# Row.net
KiCad netlist of a schematic drawn in Altium Designer
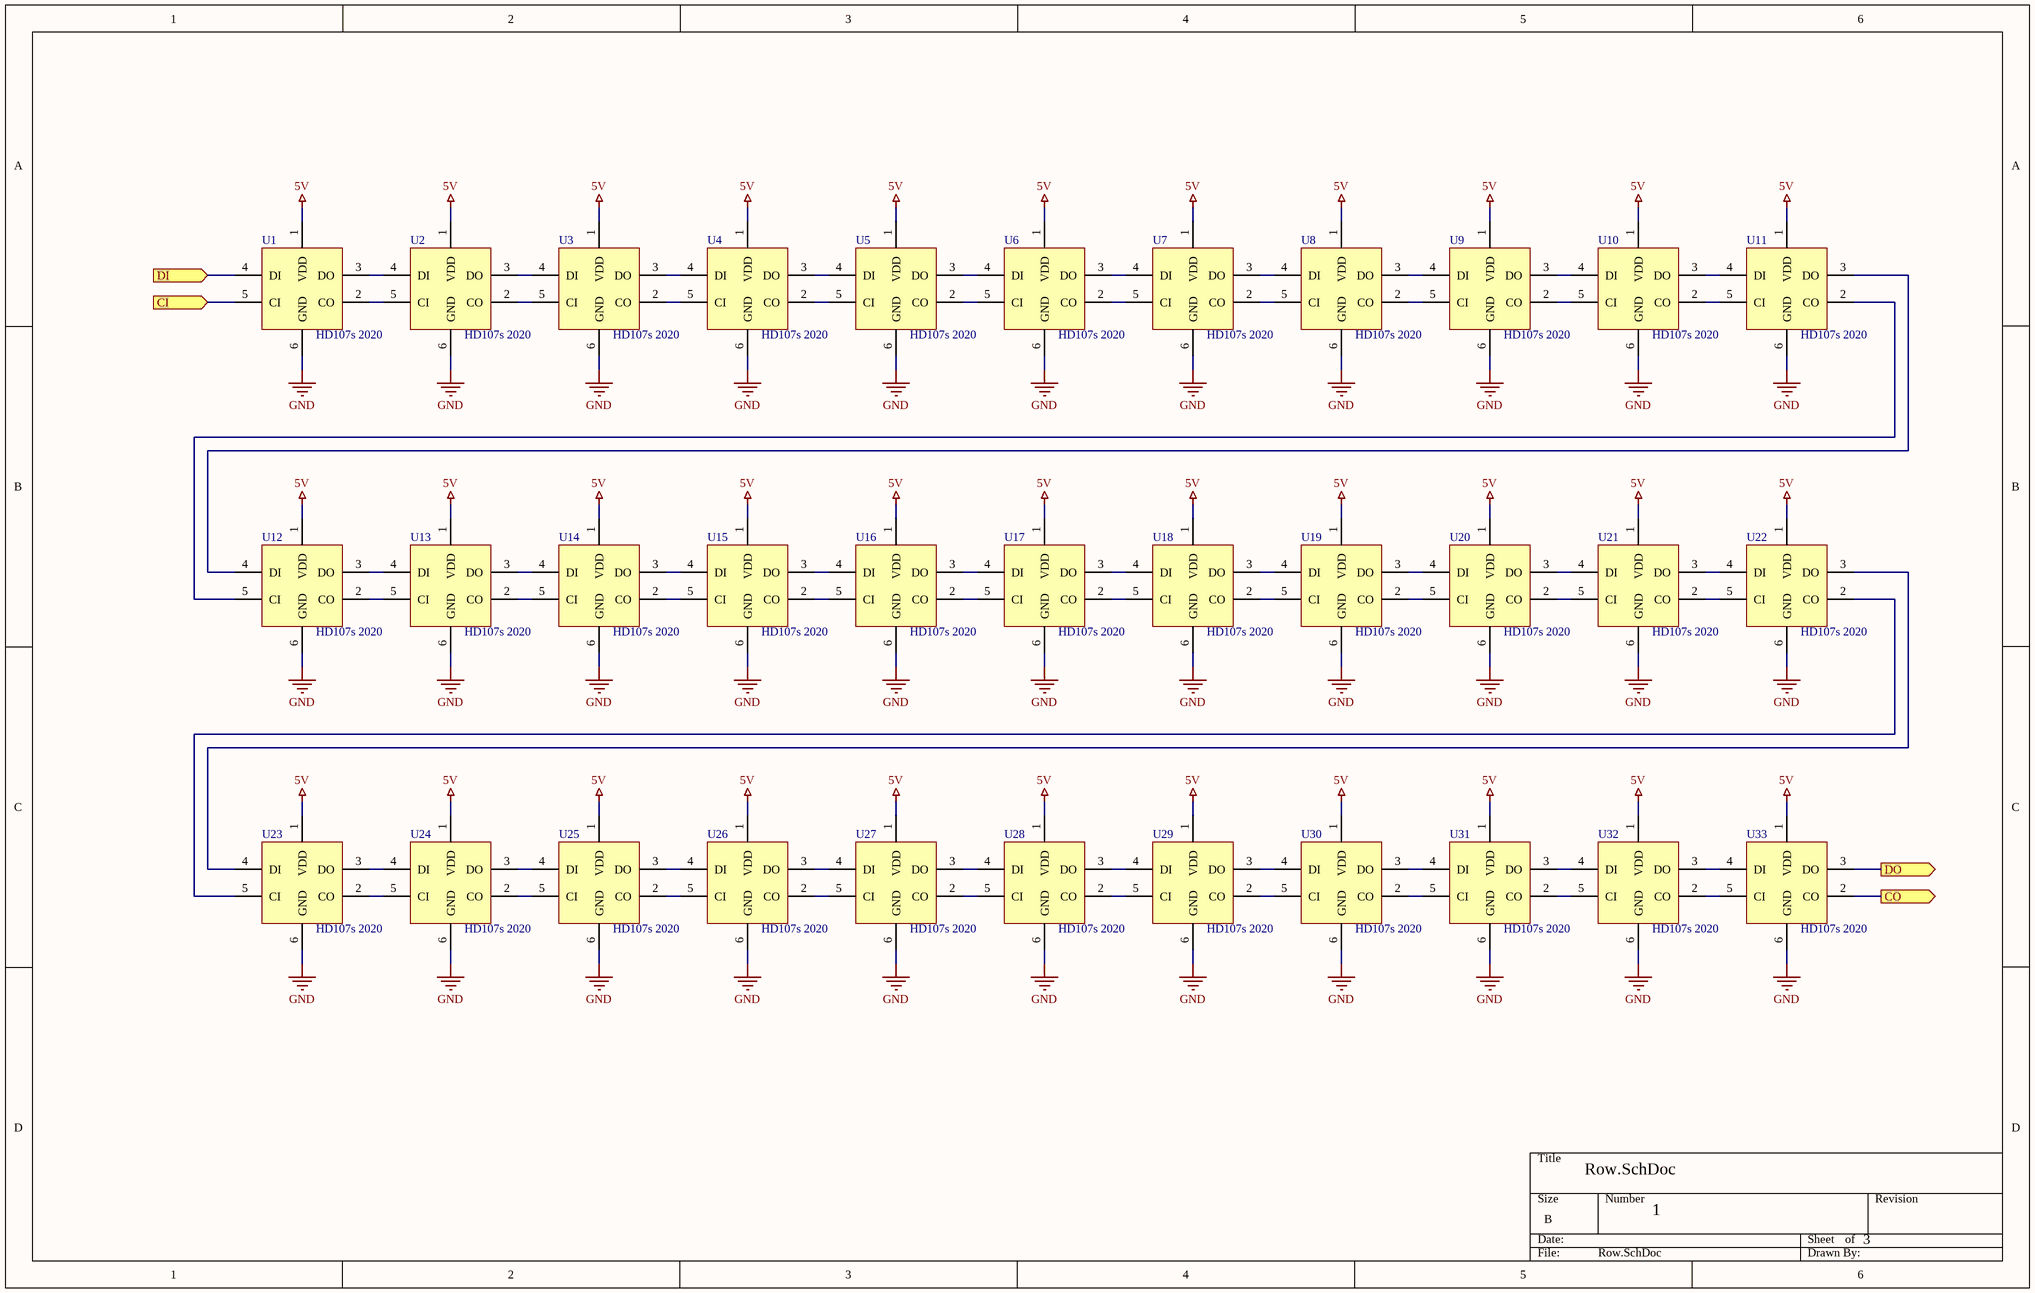
[diagram p0: Row.SchDoc]

(export (version "E")
  (design (tool "Eeschema 10.0.6"))
  (components
    (comp (ref "U1")
      (value "HD107s 2020")
      (footprint "LED_HD107s-2020")
      (description "8-pin type LED three-color RGB Dimming control")
      (fields (field (name "MP") "APA-102-2020-256-8") (field (name "MF") "iPixel LED Light Co."))
      (libsource (lib "IC") (part "HD107s-2020"))
    )
    (comp (ref "U2")
      (value "HD107s 2020")
      (footprint "LED_HD107s-2020")
      (description "8-pin type LED three-color RGB Dimming control")
      (fields (field (name "MP") "APA-102-2020-256-8") (field (name "MF") "iPixel LED Light Co."))
      (libsource (lib "IC") (part "HD107s-2020"))
    )
    (comp (ref "U3")
      (value "HD107s 2020")
      (footprint "LED_HD107s-2020")
      (description "8-pin type LED three-color RGB Dimming control")
      (fields (field (name "MP") "APA-102-2020-256-8") (field (name "MF") "iPixel LED Light Co."))
      (libsource (lib "IC") (part "HD107s-2020"))
    )
    (comp (ref "U4")
      (value "HD107s 2020")
      (footprint "LED_HD107s-2020")
      (description "8-pin type LED three-color RGB Dimming control")
      (fields (field (name "MP") "APA-102-2020-256-8") (field (name "MF") "iPixel LED Light Co."))
      (libsource (lib "IC") (part "HD107s-2020"))
    )
    (comp (ref "U5")
      (value "HD107s 2020")
      (footprint "LED_HD107s-2020")
      (description "8-pin type LED three-color RGB Dimming control")
      (fields (field (name "MP") "APA-102-2020-256-8") (field (name "MF") "iPixel LED Light Co."))
      (libsource (lib "IC") (part "HD107s-2020"))
    )
    (comp (ref "U6")
      (value "HD107s 2020")
      (footprint "LED_HD107s-2020")
      (description "8-pin type LED three-color RGB Dimming control")
      (fields (field (name "MP") "APA-102-2020-256-8") (field (name "MF") "iPixel LED Light Co."))
      (libsource (lib "IC") (part "HD107s-2020"))
    )
    (comp (ref "U7")
      (value "HD107s 2020")
      (footprint "LED_HD107s-2020")
      (description "8-pin type LED three-color RGB Dimming control")
      (fields (field (name "MP") "APA-102-2020-256-8") (field (name "MF") "iPixel LED Light Co."))
      (libsource (lib "IC") (part "HD107s-2020"))
    )
    (comp (ref "U8")
      (value "HD107s 2020")
      (footprint "LED_HD107s-2020")
      (description "8-pin type LED three-color RGB Dimming control")
      (fields (field (name "MP") "APA-102-2020-256-8") (field (name "MF") "iPixel LED Light Co."))
      (libsource (lib "IC") (part "HD107s-2020"))
    )
    (comp (ref "U9")
      (value "HD107s 2020")
      (footprint "LED_HD107s-2020")
      (description "8-pin type LED three-color RGB Dimming control")
      (fields (field (name "MP") "APA-102-2020-256-8") (field (name "MF") "iPixel LED Light Co."))
      (libsource (lib "IC") (part "HD107s-2020"))
    )
    (comp (ref "U10")
      (value "HD107s 2020")
      (footprint "LED_HD107s-2020")
      (description "8-pin type LED three-color RGB Dimming control")
      (fields (field (name "MP") "APA-102-2020-256-8") (field (name "MF") "iPixel LED Light Co."))
      (libsource (lib "IC") (part "HD107s-2020"))
    )
    (comp (ref "U11")
      (value "HD107s 2020")
      (footprint "LED_HD107s-2020")
      (description "8-pin type LED three-color RGB Dimming control")
      (fields (field (name "MP") "APA-102-2020-256-8") (field (name "MF") "iPixel LED Light Co."))
      (libsource (lib "IC") (part "HD107s-2020"))
    )
    (comp (ref "U12")
      (value "HD107s 2020")
      (footprint "LED_HD107s-2020")
      (description "8-pin type LED three-color RGB Dimming control")
      (fields (field (name "MP") "APA-102-2020-256-8") (field (name "MF") "iPixel LED Light Co."))
      (libsource (lib "IC") (part "HD107s-2020"))
    )
    (comp (ref "U13")
      (value "HD107s 2020")
      (footprint "LED_HD107s-2020")
      (description "8-pin type LED three-color RGB Dimming control")
      (fields (field (name "MP") "APA-102-2020-256-8") (field (name "MF") "iPixel LED Light Co."))
      (libsource (lib "IC") (part "HD107s-2020"))
    )
    (comp (ref "U14")
      (value "HD107s 2020")
      (footprint "LED_HD107s-2020")
      (description "8-pin type LED three-color RGB Dimming control")
      (fields (field (name "MP") "APA-102-2020-256-8") (field (name "MF") "iPixel LED Light Co."))
      (libsource (lib "IC") (part "HD107s-2020"))
    )
    (comp (ref "U15")
      (value "HD107s 2020")
      (footprint "LED_HD107s-2020")
      (description "8-pin type LED three-color RGB Dimming control")
      (fields (field (name "MP") "APA-102-2020-256-8") (field (name "MF") "iPixel LED Light Co."))
      (libsource (lib "IC") (part "HD107s-2020"))
    )
    (comp (ref "U16")
      (value "HD107s 2020")
      (footprint "LED_HD107s-2020")
      (description "8-pin type LED three-color RGB Dimming control")
      (fields (field (name "MP") "APA-102-2020-256-8") (field (name "MF") "iPixel LED Light Co."))
      (libsource (lib "IC") (part "HD107s-2020"))
    )
    (comp (ref "U17")
      (value "HD107s 2020")
      (footprint "LED_HD107s-2020")
      (description "8-pin type LED three-color RGB Dimming control")
      (fields (field (name "MP") "APA-102-2020-256-8") (field (name "MF") "iPixel LED Light Co."))
      (libsource (lib "IC") (part "HD107s-2020"))
    )
    (comp (ref "U18")
      (value "HD107s 2020")
      (footprint "LED_HD107s-2020")
      (description "8-pin type LED three-color RGB Dimming control")
      (fields (field (name "MP") "APA-102-2020-256-8") (field (name "MF") "iPixel LED Light Co."))
      (libsource (lib "IC") (part "HD107s-2020"))
    )
    (comp (ref "U19")
      (value "HD107s 2020")
      (footprint "LED_HD107s-2020")
      (description "8-pin type LED three-color RGB Dimming control")
      (fields (field (name "MP") "APA-102-2020-256-8") (field (name "MF") "iPixel LED Light Co."))
      (libsource (lib "IC") (part "HD107s-2020"))
    )
    (comp (ref "U20")
      (value "HD107s 2020")
      (footprint "LED_HD107s-2020")
      (description "8-pin type LED three-color RGB Dimming control")
      (fields (field (name "MP") "APA-102-2020-256-8") (field (name "MF") "iPixel LED Light Co."))
      (libsource (lib "IC") (part "HD107s-2020"))
    )
    (comp (ref "U21")
      (value "HD107s 2020")
      (footprint "LED_HD107s-2020")
      (description "8-pin type LED three-color RGB Dimming control")
      (fields (field (name "MP") "APA-102-2020-256-8") (field (name "MF") "iPixel LED Light Co."))
      (libsource (lib "IC") (part "HD107s-2020"))
    )
    (comp (ref "U22")
      (value "HD107s 2020")
      (footprint "LED_HD107s-2020")
      (description "8-pin type LED three-color RGB Dimming control")
      (fields (field (name "MP") "APA-102-2020-256-8") (field (name "MF") "iPixel LED Light Co."))
      (libsource (lib "IC") (part "HD107s-2020"))
    )
    (comp (ref "U23")
      (value "HD107s 2020")
      (footprint "LED_HD107s-2020")
      (description "8-pin type LED three-color RGB Dimming control")
      (fields (field (name "MP") "APA-102-2020-256-8") (field (name "MF") "iPixel LED Light Co."))
      (libsource (lib "IC") (part "HD107s-2020"))
    )
    (comp (ref "U24")
      (value "HD107s 2020")
      (footprint "LED_HD107s-2020")
      (description "8-pin type LED three-color RGB Dimming control")
      (fields (field (name "MP") "APA-102-2020-256-8") (field (name "MF") "iPixel LED Light Co."))
      (libsource (lib "IC") (part "HD107s-2020"))
    )
    (comp (ref "U25")
      (value "HD107s 2020")
      (footprint "LED_HD107s-2020")
      (description "8-pin type LED three-color RGB Dimming control")
      (fields (field (name "MP") "APA-102-2020-256-8") (field (name "MF") "iPixel LED Light Co."))
      (libsource (lib "IC") (part "HD107s-2020"))
    )
    (comp (ref "U26")
      (value "HD107s 2020")
      (footprint "LED_HD107s-2020")
      (description "8-pin type LED three-color RGB Dimming control")
      (fields (field (name "MP") "APA-102-2020-256-8") (field (name "MF") "iPixel LED Light Co."))
      (libsource (lib "IC") (part "HD107s-2020"))
    )
    (comp (ref "U27")
      (value "HD107s 2020")
      (footprint "LED_HD107s-2020")
      (description "8-pin type LED three-color RGB Dimming control")
      (fields (field (name "MP") "APA-102-2020-256-8") (field (name "MF") "iPixel LED Light Co."))
      (libsource (lib "IC") (part "HD107s-2020"))
    )
    (comp (ref "U28")
      (value "HD107s 2020")
      (footprint "LED_HD107s-2020")
      (description "8-pin type LED three-color RGB Dimming control")
      (fields (field (name "MP") "APA-102-2020-256-8") (field (name "MF") "iPixel LED Light Co."))
      (libsource (lib "IC") (part "HD107s-2020"))
    )
    (comp (ref "U29")
      (value "HD107s 2020")
      (footprint "LED_HD107s-2020")
      (description "8-pin type LED three-color RGB Dimming control")
      (fields (field (name "MP") "APA-102-2020-256-8") (field (name "MF") "iPixel LED Light Co."))
      (libsource (lib "IC") (part "HD107s-2020"))
    )
    (comp (ref "U30")
      (value "HD107s 2020")
      (footprint "LED_HD107s-2020")
      (description "8-pin type LED three-color RGB Dimming control")
      (fields (field (name "MP") "APA-102-2020-256-8") (field (name "MF") "iPixel LED Light Co."))
      (libsource (lib "IC") (part "HD107s-2020"))
    )
    (comp (ref "U31")
      (value "HD107s 2020")
      (footprint "LED_HD107s-2020")
      (description "8-pin type LED three-color RGB Dimming control")
      (fields (field (name "MP") "APA-102-2020-256-8") (field (name "MF") "iPixel LED Light Co."))
      (libsource (lib "IC") (part "HD107s-2020"))
    )
    (comp (ref "U32")
      (value "HD107s 2020")
      (footprint "LED_HD107s-2020")
      (description "8-pin type LED three-color RGB Dimming control")
      (fields (field (name "MP") "APA-102-2020-256-8") (field (name "MF") "iPixel LED Light Co."))
      (libsource (lib "IC") (part "HD107s-2020"))
    )
    (comp (ref "U33")
      (value "HD107s 2020")
      (footprint "LED_HD107s-2020")
      (description "8-pin type LED three-color RGB Dimming control")
      (fields (field (name "MP") "APA-102-2020-256-8") (field (name "MF") "iPixel LED Light Co."))
      (libsource (lib "IC") (part "HD107s-2020"))
    )
  )
  (nets
    (net (code "1") (name "/CI") (class "Default")
      (node (ref "U1") (pin "5") (pinfunction "CI_5") (pintype "passive"))
    )
    (net (code "2") (name "/CO") (class "Default")
      (node (ref "U33") (pin "2") (pinfunction "CO_2") (pintype "passive"))
    )
    (net (code "3") (name "/DI") (class "Default")
      (node (ref "U1") (pin "4") (pinfunction "DI_4") (pintype "passive"))
    )
    (net (code "4") (name "/DO") (class "Default")
      (node (ref "U33") (pin "3") (pinfunction "DO_3") (pintype "passive"))
    )
    (net (code "5") (name "5V") (class "Default")
      (node (ref "U1") (pin "1") (pinfunction "VDD_1") (pintype "power_in"))
      (node (ref "U10") (pin "1") (pinfunction "VDD_1") (pintype "power_in"))
      (node (ref "U11") (pin "1") (pinfunction "VDD_1") (pintype "power_in"))
      (node (ref "U12") (pin "1") (pinfunction "VDD_1") (pintype "power_in"))
      (node (ref "U13") (pin "1") (pinfunction "VDD_1") (pintype "power_in"))
      (node (ref "U14") (pin "1") (pinfunction "VDD_1") (pintype "power_in"))
      (node (ref "U15") (pin "1") (pinfunction "VDD_1") (pintype "power_in"))
      (node (ref "U16") (pin "1") (pinfunction "VDD_1") (pintype "power_in"))
      (node (ref "U17") (pin "1") (pinfunction "VDD_1") (pintype "power_in"))
      (node (ref "U18") (pin "1") (pinfunction "VDD_1") (pintype "power_in"))
      (node (ref "U19") (pin "1") (pinfunction "VDD_1") (pintype "power_in"))
      (node (ref "U2") (pin "1") (pinfunction "VDD_1") (pintype "power_in"))
      (node (ref "U20") (pin "1") (pinfunction "VDD_1") (pintype "power_in"))
      (node (ref "U21") (pin "1") (pinfunction "VDD_1") (pintype "power_in"))
      (node (ref "U22") (pin "1") (pinfunction "VDD_1") (pintype "power_in"))
      (node (ref "U23") (pin "1") (pinfunction "VDD_1") (pintype "power_in"))
      (node (ref "U24") (pin "1") (pinfunction "VDD_1") (pintype "power_in"))
      (node (ref "U25") (pin "1") (pinfunction "VDD_1") (pintype "power_in"))
      (node (ref "U26") (pin "1") (pinfunction "VDD_1") (pintype "power_in"))
      (node (ref "U27") (pin "1") (pinfunction "VDD_1") (pintype "power_in"))
      (node (ref "U28") (pin "1") (pinfunction "VDD_1") (pintype "power_in"))
      (node (ref "U29") (pin "1") (pinfunction "VDD_1") (pintype "power_in"))
      (node (ref "U3") (pin "1") (pinfunction "VDD_1") (pintype "power_in"))
      (node (ref "U30") (pin "1") (pinfunction "VDD_1") (pintype "power_in"))
      (node (ref "U31") (pin "1") (pinfunction "VDD_1") (pintype "power_in"))
      (node (ref "U32") (pin "1") (pinfunction "VDD_1") (pintype "power_in"))
      (node (ref "U33") (pin "1") (pinfunction "VDD_1") (pintype "power_in"))
      (node (ref "U4") (pin "1") (pinfunction "VDD_1") (pintype "power_in"))
      (node (ref "U5") (pin "1") (pinfunction "VDD_1") (pintype "power_in"))
      (node (ref "U6") (pin "1") (pinfunction "VDD_1") (pintype "power_in"))
      (node (ref "U7") (pin "1") (pinfunction "VDD_1") (pintype "power_in"))
      (node (ref "U8") (pin "1") (pinfunction "VDD_1") (pintype "power_in"))
      (node (ref "U9") (pin "1") (pinfunction "VDD_1") (pintype "power_in"))
    )
    (net (code "6") (name "GND") (class "Default")
      (node (ref "U1") (pin "6") (pinfunction "GND_6") (pintype "power_in"))
      (node (ref "U10") (pin "6") (pinfunction "GND_6") (pintype "power_in"))
      (node (ref "U11") (pin "6") (pinfunction "GND_6") (pintype "power_in"))
      (node (ref "U12") (pin "6") (pinfunction "GND_6") (pintype "power_in"))
      (node (ref "U13") (pin "6") (pinfunction "GND_6") (pintype "power_in"))
      (node (ref "U14") (pin "6") (pinfunction "GND_6") (pintype "power_in"))
      (node (ref "U15") (pin "6") (pinfunction "GND_6") (pintype "power_in"))
      (node (ref "U16") (pin "6") (pinfunction "GND_6") (pintype "power_in"))
      (node (ref "U17") (pin "6") (pinfunction "GND_6") (pintype "power_in"))
      (node (ref "U18") (pin "6") (pinfunction "GND_6") (pintype "power_in"))
      (node (ref "U19") (pin "6") (pinfunction "GND_6") (pintype "power_in"))
      (node (ref "U2") (pin "6") (pinfunction "GND_6") (pintype "power_in"))
      (node (ref "U20") (pin "6") (pinfunction "GND_6") (pintype "power_in"))
      (node (ref "U21") (pin "6") (pinfunction "GND_6") (pintype "power_in"))
      (node (ref "U22") (pin "6") (pinfunction "GND_6") (pintype "power_in"))
      (node (ref "U23") (pin "6") (pinfunction "GND_6") (pintype "power_in"))
      (node (ref "U24") (pin "6") (pinfunction "GND_6") (pintype "power_in"))
      (node (ref "U25") (pin "6") (pinfunction "GND_6") (pintype "power_in"))
      (node (ref "U26") (pin "6") (pinfunction "GND_6") (pintype "power_in"))
      (node (ref "U27") (pin "6") (pinfunction "GND_6") (pintype "power_in"))
      (node (ref "U28") (pin "6") (pinfunction "GND_6") (pintype "power_in"))
      (node (ref "U29") (pin "6") (pinfunction "GND_6") (pintype "power_in"))
      (node (ref "U3") (pin "6") (pinfunction "GND_6") (pintype "power_in"))
      (node (ref "U30") (pin "6") (pinfunction "GND_6") (pintype "power_in"))
      (node (ref "U31") (pin "6") (pinfunction "GND_6") (pintype "power_in"))
      (node (ref "U32") (pin "6") (pinfunction "GND_6") (pintype "power_in"))
      (node (ref "U33") (pin "6") (pinfunction "GND_6") (pintype "power_in"))
      (node (ref "U4") (pin "6") (pinfunction "GND_6") (pintype "power_in"))
      (node (ref "U5") (pin "6") (pinfunction "GND_6") (pintype "power_in"))
      (node (ref "U6") (pin "6") (pinfunction "GND_6") (pintype "power_in"))
      (node (ref "U7") (pin "6") (pinfunction "GND_6") (pintype "power_in"))
      (node (ref "U8") (pin "6") (pinfunction "GND_6") (pintype "power_in"))
      (node (ref "U9") (pin "6") (pinfunction "GND_6") (pintype "power_in"))
    )
    (net (code "7") (name "Net-(U1-CO)") (class "Default")
      (node (ref "U1") (pin "2") (pinfunction "CO_2") (pintype "passive"))
      (node (ref "U2") (pin "5") (pinfunction "CI_5") (pintype "passive"))
    )
    (net (code "8") (name "Net-(U1-DO)") (class "Default")
      (node (ref "U1") (pin "3") (pinfunction "DO_3") (pintype "passive"))
      (node (ref "U2") (pin "4") (pinfunction "DI_4") (pintype "passive"))
    )
    (net (code "9") (name "Net-(U2-CO)") (class "Default")
      (node (ref "U2") (pin "2") (pinfunction "CO_2") (pintype "passive"))
      (node (ref "U3") (pin "5") (pinfunction "CI_5") (pintype "passive"))
    )
    (net (code "10") (name "Net-(U2-DO)") (class "Default")
      (node (ref "U2") (pin "3") (pinfunction "DO_3") (pintype "passive"))
      (node (ref "U3") (pin "4") (pinfunction "DI_4") (pintype "passive"))
    )
    (net (code "11") (name "Net-(U3-CO)") (class "Default")
      (node (ref "U3") (pin "2") (pinfunction "CO_2") (pintype "passive"))
      (node (ref "U4") (pin "5") (pinfunction "CI_5") (pintype "passive"))
    )
    (net (code "12") (name "Net-(U3-DO)") (class "Default")
      (node (ref "U3") (pin "3") (pinfunction "DO_3") (pintype "passive"))
      (node (ref "U4") (pin "4") (pinfunction "DI_4") (pintype "passive"))
    )
    (net (code "13") (name "Net-(U4-CO)") (class "Default")
      (node (ref "U4") (pin "2") (pinfunction "CO_2") (pintype "passive"))
      (node (ref "U5") (pin "5") (pinfunction "CI_5") (pintype "passive"))
    )
    (net (code "14") (name "Net-(U4-DO)") (class "Default")
      (node (ref "U4") (pin "3") (pinfunction "DO_3") (pintype "passive"))
      (node (ref "U5") (pin "4") (pinfunction "DI_4") (pintype "passive"))
    )
    (net (code "15") (name "Net-(U5-CO)") (class "Default")
      (node (ref "U5") (pin "2") (pinfunction "CO_2") (pintype "passive"))
      (node (ref "U6") (pin "5") (pinfunction "CI_5") (pintype "passive"))
    )
    (net (code "16") (name "Net-(U5-DO)") (class "Default")
      (node (ref "U5") (pin "3") (pinfunction "DO_3") (pintype "passive"))
      (node (ref "U6") (pin "4") (pinfunction "DI_4") (pintype "passive"))
    )
    (net (code "17") (name "Net-(U6-CO)") (class "Default")
      (node (ref "U6") (pin "2") (pinfunction "CO_2") (pintype "passive"))
      (node (ref "U7") (pin "5") (pinfunction "CI_5") (pintype "passive"))
    )
    (net (code "18") (name "Net-(U6-DO)") (class "Default")
      (node (ref "U6") (pin "3") (pinfunction "DO_3") (pintype "passive"))
      (node (ref "U7") (pin "4") (pinfunction "DI_4") (pintype "passive"))
    )
    (net (code "19") (name "Net-(U7-CO)") (class "Default")
      (node (ref "U7") (pin "2") (pinfunction "CO_2") (pintype "passive"))
      (node (ref "U8") (pin "5") (pinfunction "CI_5") (pintype "passive"))
    )
    (net (code "20") (name "Net-(U7-DO)") (class "Default")
      (node (ref "U7") (pin "3") (pinfunction "DO_3") (pintype "passive"))
      (node (ref "U8") (pin "4") (pinfunction "DI_4") (pintype "passive"))
    )
    (net (code "21") (name "Net-(U8-CO)") (class "Default")
      (node (ref "U8") (pin "2") (pinfunction "CO_2") (pintype "passive"))
      (node (ref "U9") (pin "5") (pinfunction "CI_5") (pintype "passive"))
    )
    (net (code "22") (name "Net-(U8-DO)") (class "Default")
      (node (ref "U8") (pin "3") (pinfunction "DO_3") (pintype "passive"))
      (node (ref "U9") (pin "4") (pinfunction "DI_4") (pintype "passive"))
    )
    (net (code "23") (name "Net-(U10-CI)") (class "Default")
      (node (ref "U10") (pin "5") (pinfunction "CI_5") (pintype "passive"))
      (node (ref "U9") (pin "2") (pinfunction "CO_2") (pintype "passive"))
    )
    (net (code "24") (name "Net-(U10-CO)") (class "Default")
      (node (ref "U10") (pin "2") (pinfunction "CO_2") (pintype "passive"))
      (node (ref "U11") (pin "5") (pinfunction "CI_5") (pintype "passive"))
    )
    (net (code "25") (name "Net-(U10-DI)") (class "Default")
      (node (ref "U10") (pin "4") (pinfunction "DI_4") (pintype "passive"))
      (node (ref "U9") (pin "3") (pinfunction "DO_3") (pintype "passive"))
    )
    (net (code "26") (name "Net-(U10-DO)") (class "Default")
      (node (ref "U10") (pin "3") (pinfunction "DO_3") (pintype "passive"))
      (node (ref "U11") (pin "4") (pinfunction "DI_4") (pintype "passive"))
    )
    (net (code "27") (name "Net-(U11-CO)") (class "Default")
      (node (ref "U11") (pin "2") (pinfunction "CO_2") (pintype "passive"))
      (node (ref "U12") (pin "5") (pinfunction "CI_5") (pintype "passive"))
    )
    (net (code "28") (name "Net-(U11-DO)") (class "Default")
      (node (ref "U11") (pin "3") (pinfunction "DO_3") (pintype "passive"))
      (node (ref "U12") (pin "4") (pinfunction "DI_4") (pintype "passive"))
    )
    (net (code "29") (name "Net-(U12-CO)") (class "Default")
      (node (ref "U12") (pin "2") (pinfunction "CO_2") (pintype "passive"))
      (node (ref "U13") (pin "5") (pinfunction "CI_5") (pintype "passive"))
    )
    (net (code "30") (name "Net-(U12-DO)") (class "Default")
      (node (ref "U12") (pin "3") (pinfunction "DO_3") (pintype "passive"))
      (node (ref "U13") (pin "4") (pinfunction "DI_4") (pintype "passive"))
    )
    (net (code "31") (name "Net-(U13-CO)") (class "Default")
      (node (ref "U13") (pin "2") (pinfunction "CO_2") (pintype "passive"))
      (node (ref "U14") (pin "5") (pinfunction "CI_5") (pintype "passive"))
    )
    (net (code "32") (name "Net-(U13-DO)") (class "Default")
      (node (ref "U13") (pin "3") (pinfunction "DO_3") (pintype "passive"))
      (node (ref "U14") (pin "4") (pinfunction "DI_4") (pintype "passive"))
    )
    (net (code "33") (name "Net-(U14-CO)") (class "Default")
      (node (ref "U14") (pin "2") (pinfunction "CO_2") (pintype "passive"))
      (node (ref "U15") (pin "5") (pinfunction "CI_5") (pintype "passive"))
    )
    (net (code "34") (name "Net-(U14-DO)") (class "Default")
      (node (ref "U14") (pin "3") (pinfunction "DO_3") (pintype "passive"))
      (node (ref "U15") (pin "4") (pinfunction "DI_4") (pintype "passive"))
    )
    (net (code "35") (name "Net-(U15-CO)") (class "Default")
      (node (ref "U15") (pin "2") (pinfunction "CO_2") (pintype "passive"))
      (node (ref "U16") (pin "5") (pinfunction "CI_5") (pintype "passive"))
    )
    (net (code "36") (name "Net-(U15-DO)") (class "Default")
      (node (ref "U15") (pin "3") (pinfunction "DO_3") (pintype "passive"))
      (node (ref "U16") (pin "4") (pinfunction "DI_4") (pintype "passive"))
    )
    (net (code "37") (name "Net-(U16-CO)") (class "Default")
      (node (ref "U16") (pin "2") (pinfunction "CO_2") (pintype "passive"))
      (node (ref "U17") (pin "5") (pinfunction "CI_5") (pintype "passive"))
    )
    (net (code "38") (name "Net-(U16-DO)") (class "Default")
      (node (ref "U16") (pin "3") (pinfunction "DO_3") (pintype "passive"))
      (node (ref "U17") (pin "4") (pinfunction "DI_4") (pintype "passive"))
    )
    (net (code "39") (name "Net-(U17-CO)") (class "Default")
      (node (ref "U17") (pin "2") (pinfunction "CO_2") (pintype "passive"))
      (node (ref "U18") (pin "5") (pinfunction "CI_5") (pintype "passive"))
    )
    (net (code "40") (name "Net-(U17-DO)") (class "Default")
      (node (ref "U17") (pin "3") (pinfunction "DO_3") (pintype "passive"))
      (node (ref "U18") (pin "4") (pinfunction "DI_4") (pintype "passive"))
    )
    (net (code "41") (name "Net-(U18-CO)") (class "Default")
      (node (ref "U18") (pin "2") (pinfunction "CO_2") (pintype "passive"))
      (node (ref "U19") (pin "5") (pinfunction "CI_5") (pintype "passive"))
    )
    (net (code "42") (name "Net-(U18-DO)") (class "Default")
      (node (ref "U18") (pin "3") (pinfunction "DO_3") (pintype "passive"))
      (node (ref "U19") (pin "4") (pinfunction "DI_4") (pintype "passive"))
    )
    (net (code "43") (name "Net-(U19-CO)") (class "Default")
      (node (ref "U19") (pin "2") (pinfunction "CO_2") (pintype "passive"))
      (node (ref "U20") (pin "5") (pinfunction "CI_5") (pintype "passive"))
    )
    (net (code "44") (name "Net-(U19-DO)") (class "Default")
      (node (ref "U19") (pin "3") (pinfunction "DO_3") (pintype "passive"))
      (node (ref "U20") (pin "4") (pinfunction "DI_4") (pintype "passive"))
    )
    (net (code "45") (name "Net-(U20-CO)") (class "Default")
      (node (ref "U20") (pin "2") (pinfunction "CO_2") (pintype "passive"))
      (node (ref "U21") (pin "5") (pinfunction "CI_5") (pintype "passive"))
    )
    (net (code "46") (name "Net-(U20-DO)") (class "Default")
      (node (ref "U20") (pin "3") (pinfunction "DO_3") (pintype "passive"))
      (node (ref "U21") (pin "4") (pinfunction "DI_4") (pintype "passive"))
    )
    (net (code "47") (name "Net-(U21-CO)") (class "Default")
      (node (ref "U21") (pin "2") (pinfunction "CO_2") (pintype "passive"))
      (node (ref "U22") (pin "5") (pinfunction "CI_5") (pintype "passive"))
    )
    (net (code "48") (name "Net-(U21-DO)") (class "Default")
      (node (ref "U21") (pin "3") (pinfunction "DO_3") (pintype "passive"))
      (node (ref "U22") (pin "4") (pinfunction "DI_4") (pintype "passive"))
    )
    (net (code "49") (name "Net-(U22-CO)") (class "Default")
      (node (ref "U22") (pin "2") (pinfunction "CO_2") (pintype "passive"))
      (node (ref "U23") (pin "5") (pinfunction "CI_5") (pintype "passive"))
    )
    (net (code "50") (name "Net-(U22-DO)") (class "Default")
      (node (ref "U22") (pin "3") (pinfunction "DO_3") (pintype "passive"))
      (node (ref "U23") (pin "4") (pinfunction "DI_4") (pintype "passive"))
    )
    (net (code "51") (name "Net-(U23-CO)") (class "Default")
      (node (ref "U23") (pin "2") (pinfunction "CO_2") (pintype "passive"))
      (node (ref "U24") (pin "5") (pinfunction "CI_5") (pintype "passive"))
    )
    (net (code "52") (name "Net-(U23-DO)") (class "Default")
      (node (ref "U23") (pin "3") (pinfunction "DO_3") (pintype "passive"))
      (node (ref "U24") (pin "4") (pinfunction "DI_4") (pintype "passive"))
    )
    (net (code "53") (name "Net-(U24-CO)") (class "Default")
      (node (ref "U24") (pin "2") (pinfunction "CO_2") (pintype "passive"))
      (node (ref "U25") (pin "5") (pinfunction "CI_5") (pintype "passive"))
    )
    (net (code "54") (name "Net-(U24-DO)") (class "Default")
      (node (ref "U24") (pin "3") (pinfunction "DO_3") (pintype "passive"))
      (node (ref "U25") (pin "4") (pinfunction "DI_4") (pintype "passive"))
    )
    (net (code "55") (name "Net-(U25-CO)") (class "Default")
      (node (ref "U25") (pin "2") (pinfunction "CO_2") (pintype "passive"))
      (node (ref "U26") (pin "5") (pinfunction "CI_5") (pintype "passive"))
    )
    (net (code "56") (name "Net-(U25-DO)") (class "Default")
      (node (ref "U25") (pin "3") (pinfunction "DO_3") (pintype "passive"))
      (node (ref "U26") (pin "4") (pinfunction "DI_4") (pintype "passive"))
    )
    (net (code "57") (name "Net-(U26-CO)") (class "Default")
      (node (ref "U26") (pin "2") (pinfunction "CO_2") (pintype "passive"))
      (node (ref "U27") (pin "5") (pinfunction "CI_5") (pintype "passive"))
    )
    (net (code "58") (name "Net-(U26-DO)") (class "Default")
      (node (ref "U26") (pin "3") (pinfunction "DO_3") (pintype "passive"))
      (node (ref "U27") (pin "4") (pinfunction "DI_4") (pintype "passive"))
    )
    (net (code "59") (name "Net-(U27-CO)") (class "Default")
      (node (ref "U27") (pin "2") (pinfunction "CO_2") (pintype "passive"))
      (node (ref "U28") (pin "5") (pinfunction "CI_5") (pintype "passive"))
    )
    (net (code "60") (name "Net-(U27-DO)") (class "Default")
      (node (ref "U27") (pin "3") (pinfunction "DO_3") (pintype "passive"))
      (node (ref "U28") (pin "4") (pinfunction "DI_4") (pintype "passive"))
    )
    (net (code "61") (name "Net-(U28-CO)") (class "Default")
      (node (ref "U28") (pin "2") (pinfunction "CO_2") (pintype "passive"))
      (node (ref "U29") (pin "5") (pinfunction "CI_5") (pintype "passive"))
    )
    (net (code "62") (name "Net-(U28-DO)") (class "Default")
      (node (ref "U28") (pin "3") (pinfunction "DO_3") (pintype "passive"))
      (node (ref "U29") (pin "4") (pinfunction "DI_4") (pintype "passive"))
    )
    (net (code "63") (name "Net-(U29-CO)") (class "Default")
      (node (ref "U29") (pin "2") (pinfunction "CO_2") (pintype "passive"))
      (node (ref "U30") (pin "5") (pinfunction "CI_5") (pintype "passive"))
    )
    (net (code "64") (name "Net-(U29-DO)") (class "Default")
      (node (ref "U29") (pin "3") (pinfunction "DO_3") (pintype "passive"))
      (node (ref "U30") (pin "4") (pinfunction "DI_4") (pintype "passive"))
    )
    (net (code "65") (name "Net-(U30-CO)") (class "Default")
      (node (ref "U30") (pin "2") (pinfunction "CO_2") (pintype "passive"))
      (node (ref "U31") (pin "5") (pinfunction "CI_5") (pintype "passive"))
    )
    (net (code "66") (name "Net-(U30-DO)") (class "Default")
      (node (ref "U30") (pin "3") (pinfunction "DO_3") (pintype "passive"))
      (node (ref "U31") (pin "4") (pinfunction "DI_4") (pintype "passive"))
    )
    (net (code "67") (name "Net-(U31-CO)") (class "Default")
      (node (ref "U31") (pin "2") (pinfunction "CO_2") (pintype "passive"))
      (node (ref "U32") (pin "5") (pinfunction "CI_5") (pintype "passive"))
    )
    (net (code "68") (name "Net-(U31-DO)") (class "Default")
      (node (ref "U31") (pin "3") (pinfunction "DO_3") (pintype "passive"))
      (node (ref "U32") (pin "4") (pinfunction "DI_4") (pintype "passive"))
    )
    (net (code "69") (name "Net-(U32-CO)") (class "Default")
      (node (ref "U32") (pin "2") (pinfunction "CO_2") (pintype "passive"))
      (node (ref "U33") (pin "5") (pinfunction "CI_5") (pintype "passive"))
    )
    (net (code "70") (name "Net-(U32-DO)") (class "Default")
      (node (ref "U32") (pin "3") (pinfunction "DO_3") (pintype "passive"))
      (node (ref "U33") (pin "4") (pinfunction "DI_4") (pintype "passive"))
    )
  )
)
